# top.net
KiCad netlist of a schematic drawn in Altium Designer
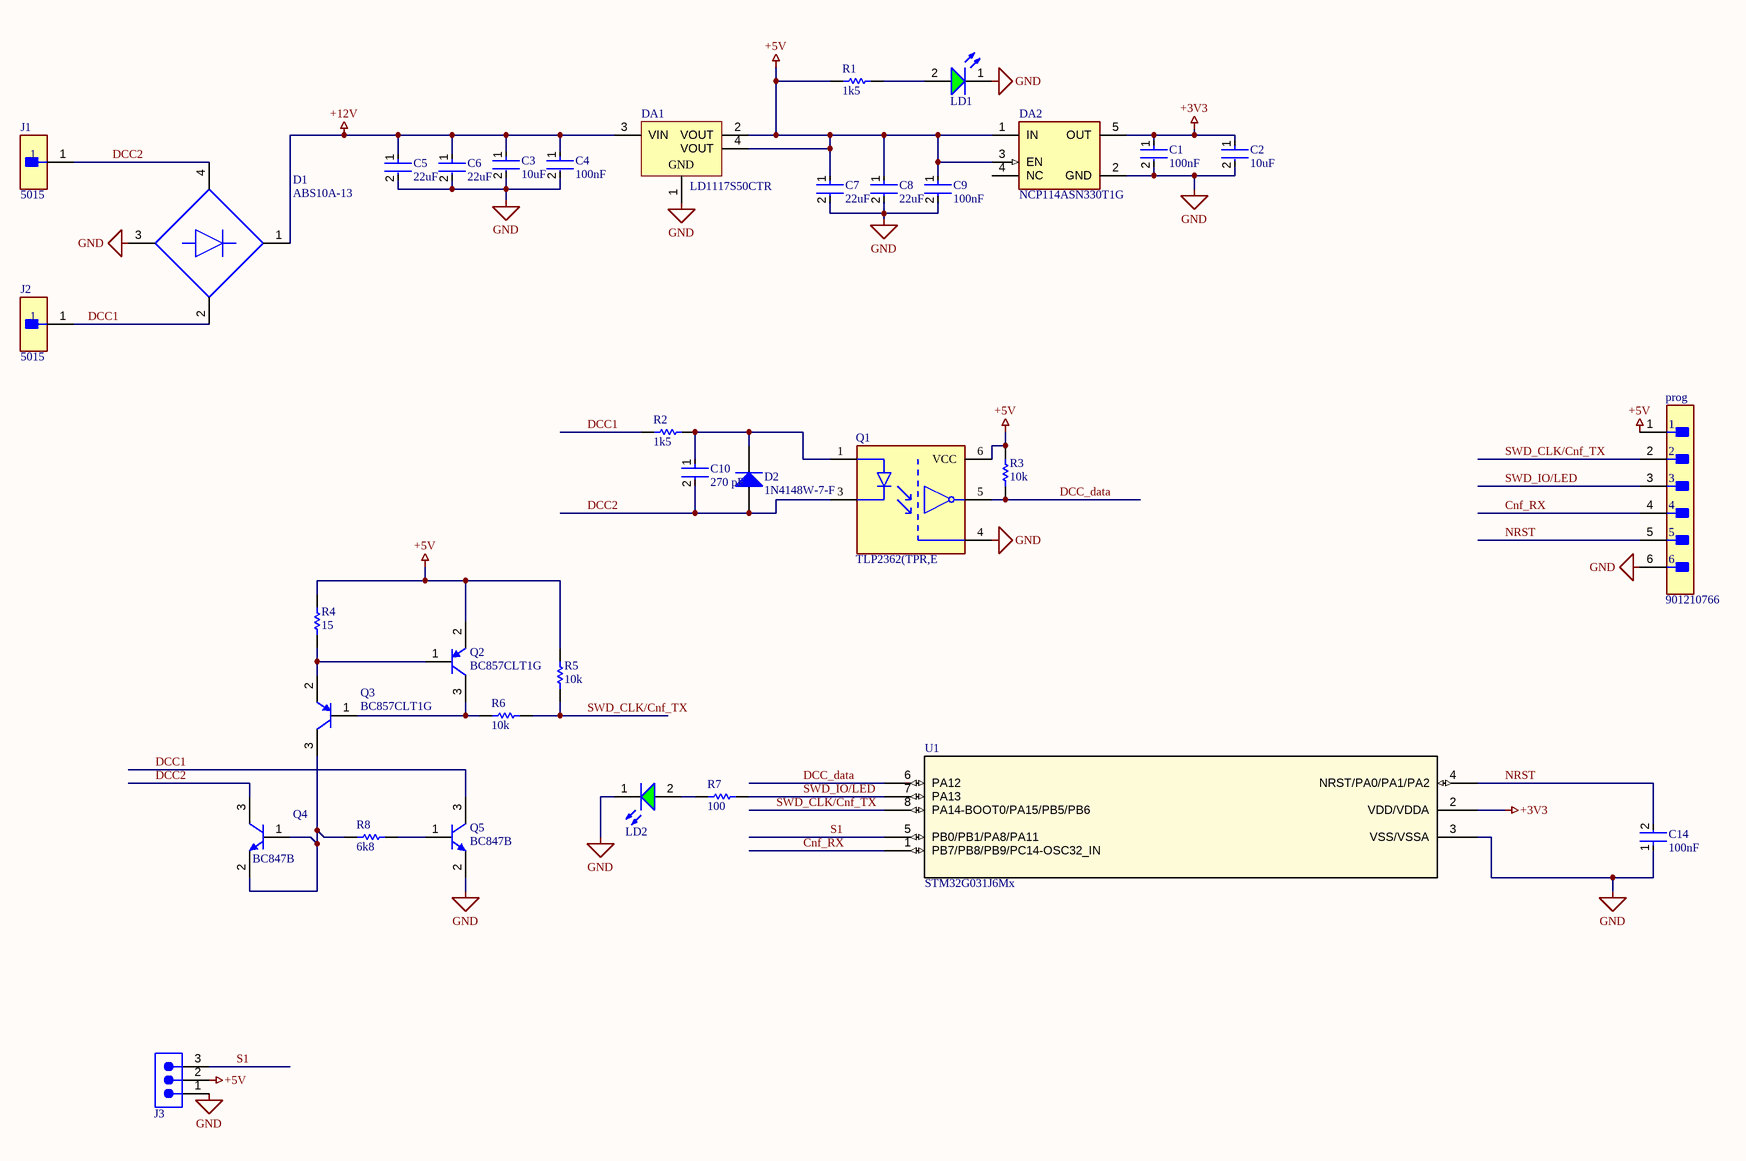
[diagram p0: top.SchDoc]

(export (version "E")
  (design (tool "Eeschema 10.0.6"))
  (components
    (comp (ref "C1")
      (value "CGA3E2X7R1H104K080AA")
      (footprint "FP-CGA3E-0_3-0_1-MFG")
      (description "Cap Ceramic 100nF 50V X7R 10% Pad SMD 0603 +125°C Automotive T/R")
      (fields
        (field (name "TOLERANCE") "10%")
        (field (name "CAPACITANCE") "100nF")
        (field (name "VOLTAGE") "50V")
      )
      (libsource (lib "Altium Content Vault") (part "b4654b650e69147ec39a6b967a45e02"))
    )
    (comp (ref "C2")
      (value "GRM188R60J106ME47D")
      (footprint "FP-GRM188-0_1-e0_2_0_55-MFG")
      (description "Chip Multilayer Ceramic Capacitors for General Purpose, 0603, 10uF, X5R, 15%, 20%, 6.3V")
      (fields
        (field (name "CAPACITANCE") "10uF")
        (field (name "VOLTAGE") "6.3V")
        (field (name "TOLERANCE") "20%")
      )
      (libsource (lib "Altium Content Vault") (part "02cd4be3c70576c341d710602a673aa"))
    )
    (comp (ref "C3")
      (value "GRM188R60J106ME47D")
      (footprint "FP-GRM188-0_1-e0_2_0_55-MFG")
      (description "Chip Multilayer Ceramic Capacitors for General Purpose, 0603, 10uF, X5R, 15%, 20%, 6.3V")
      (fields
        (field (name "CAPACITANCE") "10uF")
        (field (name "VOLTAGE") "6.3V")
        (field (name "TOLERANCE") "20%")
      )
      (libsource (lib "Altium Content Vault") (part "02cd4be3c70576c341d710602a673aa"))
    )
    (comp (ref "C4")
      (value "CGA3E2X7R1H104K080AA")
      (footprint "FP-CGA3E-0_3-0_1-MFG")
      (description "Cap Ceramic 100nF 50V X7R 10% Pad SMD 0603 +125°C Automotive T/R")
      (fields
        (field (name "TOLERANCE") "10%")
        (field (name "CAPACITANCE") "100nF")
        (field (name "VOLTAGE") "50V")
      )
      (libsource (lib "Altium Content Vault") (part "b4654b650e69147ec39a6b967a45e02"))
    )
    (comp (ref "C5")
      (value "GRM188R61A226ME15D")
      (footprint "FP-GRM188-0_2-MFG")
      (description "Chip Multilayer Ceramic Capacitors for General Purpose, 0603, 22uF, X5R, 15%, 20%, 10V")
      (fields (field (name "TOLERANCE") "20%") (field (name "CAPACITANCE") "22uF"))
      (libsource (lib "Altium Content Vault") (part "11868f565c42a9108669ba33697ecf6"))
    )
    (comp (ref "C6")
      (value "GRM188R61A226ME15D")
      (footprint "FP-GRM188-0_2-MFG")
      (description "Chip Multilayer Ceramic Capacitors for General Purpose, 0603, 22uF, X5R, 15%, 20%, 10V")
      (fields (field (name "TOLERANCE") "20%") (field (name "CAPACITANCE") "22uF"))
      (libsource (lib "Altium Content Vault") (part "11868f565c42a9108669ba33697ecf6"))
    )
    (comp (ref "C7")
      (value "GRM188R61A226ME15D")
      (footprint "FP-GRM188-0_2-MFG")
      (description "Chip Multilayer Ceramic Capacitors for General Purpose, 0603, 22uF, X5R, 15%, 20%, 10V")
      (fields (field (name "TOLERANCE") "20%") (field (name "CAPACITANCE") "22uF"))
      (libsource (lib "Altium Content Vault") (part "11868f565c42a9108669ba33697ecf6"))
    )
    (comp (ref "C8")
      (value "GRM188R61A226ME15D")
      (footprint "FP-GRM188-0_2-MFG")
      (description "Chip Multilayer Ceramic Capacitors for General Purpose, 0603, 22uF, X5R, 15%, 20%, 10V")
      (fields (field (name "TOLERANCE") "20%") (field (name "CAPACITANCE") "22uF"))
      (libsource (lib "Altium Content Vault") (part "11868f565c42a9108669ba33697ecf6"))
    )
    (comp (ref "C9")
      (value "CGA3E2X7R1H104K080AA")
      (footprint "FP-CGA3E-0_3-0_1-MFG")
      (description "Cap Ceramic 100nF 50V X7R 10% Pad SMD 0603 +125°C Automotive T/R")
      (fields
        (field (name "TOLERANCE") "10%")
        (field (name "CAPACITANCE") "100nF")
        (field (name "VOLTAGE") "50V")
      )
      (libsource (lib "Altium Content Vault") (part "b4654b650e69147ec39a6b967a45e02"))
    )
    (comp (ref "C10")
      (value "270 pF")
      (footprint "FP-C0603C-CF-IPC_C")
      (description "C0603 270 pF C0G 30ppm/°C 5.00% 50 V")
      (fields (field (name "MANUFACTURER PART NUMBER") "C0603C271J5GACTU"))
      (libsource (lib "Altium Content Vault") (part "b4654b650e69147ec39a6b967a45e02"))
    )
    (comp (ref "C14")
      (value "CGA3E2X7R1H104K080AA")
      (footprint "FP-CGA3E-0_3-0_1-MFG")
      (description "Cap Ceramic 100nF 50V X7R 10% Pad SMD 0603 +125°C Automotive T/R")
      (fields
        (field (name "TOLERANCE") "10%")
        (field (name "CAPACITANCE") "100nF")
        (field (name "VOLTAGE") "50V")
      )
      (libsource (lib "Altium Content Vault") (part "b4654b650e69147ec39a6b967a45e02"))
    )
    (comp (ref "D1")
      (value "ABS10A-13")
      (footprint "FP-SOPA-4-MFG")
      (description "BRIDGE RECT 1PHASE 1KV 1A 4SOPA")
      (libsource (lib "Altium Content Vault") (part "95261e4f58a5ffcdc7f7244183d0b96"))
    )
    (comp (ref "D2")
      (value "1N4148W-7-F")
      (footprint "DIOD-SOD123-2_V")
      (description "Fast Switching Diode, 100 V, 0.15 A, -65 to 150 degC, 2-Pin?SOD123, RoHS, Tape and Reel")
      (fields (field (name "MANUFACTURER") "DiodesIncorporated"))
      (libsource (lib "Altium Content Vault") (part "D-AK-2"))
    )
    (comp (ref "DA1")
      (value "LD1117S50CTR")
      (footprint "SOT-223_N")
      (description "Fixed Low Drop Positive Voltage Regulator, 5V, 4-Pin SOT-223, Tape and Reel")
      (libsource (lib "Altium Content Vault") (part "PM-REG-LD1117-SOT4"))
    )
    (comp (ref "DA2")
      (value "NCP114ASN330T1G")
      (footprint "FP-483-MFG")
      (description "IC REG LINEAR 3.3V 300MA 5TSOP")
      (fields
        (field (name "MANUFACTURER") "ON Semiconductor")
        (field (name "OCTOPART") "https://octopart.com/ncp114asn330t1g-on+semiconductor-74628742")
      )
      (libsource (lib "Altium Content Vault") (part "57814aa37072aacea77ef0fe9350350"))
    )
    (comp (ref "J1")
      (value "5015")
      (footprint "FP-5015-MFG")
      (description "PC TEST POINT MINIATURE")
      (fields
        (field (name "MANUFACTURER") "keystone")
        (field (name "OCTOPART") "https://octopart.com/5015-keystone-3822")
      )
      (libsource (lib "Altium Content Vault") (part "dd45045ce8184df9e99e12baf3f412c"))
    )
    (comp (ref "J2")
      (value "5015")
      (footprint "FP-5015-MFG")
      (description "PC TEST POINT MINIATURE")
      (fields
        (field (name "MANUFACTURER") "keystone")
        (field (name "OCTOPART") "https://octopart.com/5015-keystone-3822")
      )
      (libsource (lib "Altium Content Vault") (part "dd45045ce8184df9e99e12baf3f412c"))
    )
    (comp (ref "J3")
      (value "61300311021")
      (footprint "61300311021")
      (libsource (lib "Altium Content Vault") (part "Header_Male_1R_03P"))
    )
    (comp (ref "LD1")
      (value "150060VS75000")
      (footprint "WL-SMCW_0603_150060xx75000")
      (description "WURTH ELEKTRONIK - 150060VS75000 - LED, Green, SMD, 0603, 30 mA, 2 V, 570 nm")
      (libsource (lib "Altium Content Vault") (part "LED_Green_2A-1K"))
    )
    (comp (ref "LD2")
      (value "150060VS75000")
      (footprint "WL-SMCW_0603_150060xx75000")
      (description "WURTH ELEKTRONIK - 150060VS75000 - LED, Green, SMD, 0603, 30 mA, 2 V, 570 nm")
      (libsource (lib "Altium Content Vault") (part "LED_Green_2A-1K"))
    )
    (comp (ref "prog")
      (value "901210766")
      (footprint "FP-901210766-MFG")
      (description "CONN HEADER R/A 6POS 2.54MM")
      (fields
        (field (name "MANUFACTURER") "Molex")
        (field (name "OCTOPART") "https://octopart.com/90121-0766-molex-655456")
      )
      (libsource (lib "Altium Content Vault") (part "f2cb566baf1c37ab5a3b8e90bbeafd6"))
    )
    (comp (ref "Q1")
      (value "TLP2362(TPR,E")
      (footprint "FP-11-4L1S-MFG")
      (description "OPTOISO 3.75KV OPEN COLL SO6-5")
      (libsource (lib "Altium Content Vault") (part "1791dc5a774169b38fe9388fa91af9f"))
    )
    (comp (ref "Q2")
      (value "BC857CLT1G")
      (footprint "ONSC-SOT-23-3-318-08_V")
      (description "General Purpose Transistor, PNP Silicon, 3-Pin SOT-23, Pb-Free, Tape and Reel")
      (fields (field (name "MANUFACTURER") "On Semiconductor"))
      (libsource (lib "Altium Content Vault") (part "ONSC-PNP-B1E2C3-3"))
    )
    (comp (ref "Q3")
      (value "BC857CLT1G")
      (footprint "ONSC-SOT-23-3-318-08_V")
      (description "General Purpose Transistor, PNP Silicon, 3-Pin SOT-23, Pb-Free, Tape and Reel")
      (fields (field (name "MANUFACTURER") "On Semiconductor"))
      (libsource (lib "Altium Content Vault") (part "ONSC-PNP-B1E2C3-3"))
    )
    (comp (ref "Q4")
      (value "BC847B")
      (footprint "INF-SOT23_M")
      (description "NPN Silicon AF Transistor, 45 V VCEO, 100 mA IC, SOT23, Reel, Green")
      (fields (field (name "MANUFACTURER") "Infineon"))
      (libsource (lib "Altium Content Vault") (part "INF-BJTNPN-BEC-3"))
    )
    (comp (ref "Q5")
      (value "BC847B")
      (footprint "INF-SOT23_M")
      (description "NPN Silicon AF Transistor, 45 V VCEO, 100 mA IC, SOT23, Reel, Green")
      (fields (field (name "MANUFACTURER") "Infineon"))
      (libsource (lib "Altium Content Vault") (part "INF-BJTNPN-BEC-3"))
    )
    (comp (ref "R1")
      (value "1k5")
      (footprint "RESC1608X55X25ML10T15")
      (description "Chip Resistor, 1.5 KOhm, +/- 1%, 0.1 W, -55 to 155 degC, 0603 (1608 Metric), RoHS, Tape and Reel")
      (fields (field (name "TOLERANCE") "1%") (field (name "MANUFACTURER") "Yageo"))
      (libsource (lib "Altium Content Vault") (part "RES-2"))
    )
    (comp (ref "R2")
      (value "1k5")
      (footprint "RESC1608X55X25ML10T15")
      (description "Chip Resistor, 1.5 KOhm, +/- 1%, 0.1 W, -55 to 155 degC, 0603 (1608 Metric), RoHS, Tape and Reel")
      (fields (field (name "TOLERANCE") "1%") (field (name "MANUFACTURER") "Yageo"))
      (libsource (lib "Altium Content Vault") (part "RES-2"))
    )
    (comp (ref "R3")
      (value "10k")
      (footprint "RESC1609X55X30NL15T15")
      (description "Chip Resistor, 10 KOhm, +/- 1%, 0.1 W, -55 to 155 degC, 0603 (1608 Metric), RoHS, Tape and Reel")
      (fields (field (name "TOLERANCE") "1%") (field (name "MANUFACTURER") "Panasonic"))
      (libsource (lib "Altium Content Vault") (part "RES-2"))
    )
    (comp (ref "R4")
      (value "15")
      (footprint "RESC1608X55X30NL15T15")
      (fields (field (name "PART NUMBER") "ERJ-3EKF1502V") (field (name "MANUFACTURER") "Panasonic"))
      (libsource (lib "Altium Content Vault") (part "RES"))
    )
    (comp (ref "R5")
      (value "10k")
      (footprint "RESC1609X55X30NL15T15")
      (description "Chip Resistor, 10 KOhm, +/- 1%, 0.1 W, -55 to 155 degC, 0603 (1608 Metric), RoHS, Tape and Reel")
      (fields (field (name "TOLERANCE") "1%") (field (name "MANUFACTURER") "Panasonic"))
      (libsource (lib "Altium Content Vault") (part "RES-2"))
    )
    (comp (ref "R6")
      (value "10k")
      (footprint "RESC1609X55X30NL15T15")
      (description "Chip Resistor, 10 KOhm, +/- 1%, 0.1 W, -55 to 155 degC, 0603 (1608 Metric), RoHS, Tape and Reel")
      (fields (field (name "TOLERANCE") "1%") (field (name "MANUFACTURER") "Panasonic"))
      (libsource (lib "Altium Content Vault") (part "RES-2"))
    )
    (comp (ref "R7")
      (value "100")
      (footprint "RESC1608X55X30NL15T15")
      (fields (field (name "PART NUMBER") "ERJ-3EKF1003V") (field (name "MANUFACTURER") "Panasonic"))
      (libsource (lib "Altium Content Vault") (part "RES"))
    )
    (comp (ref "R8")
      (value "6k8")
      (footprint "RESC1608X55X25NL10T15")
      (description "Chip Resistor, 6.8 KOhm, +/- 1%, 100 mW, -55 to 155 degC, 0603 (1608 Metric), RoHS, Tape and Reel")
      (fields (field (name "Comment") "RC0603FR-076K8L"))
      (libsource (lib "Altium Content Vault") (part "RES-2"))
    )
    (comp (ref "U1")
      (value "STM32G031J6Mx")
      (footprint "SO-8")
      (fields
        (field (name "MANUFACTURER_PART_NUMBER") "stm32g0_so8_t1")
        (field (name "COPYRIGHT") "Copyright (C) 2018 Accelerated Designs. All rights reserved")
      )
      (libsource (lib "ST Microelectronics STM32 G0") (part "STM32G031J6Mx"))
    )
  )
  (nets
    (net (code "1") (name "+3V3") (class "Default")
      (node (ref "C1") (pin "1") (pinfunction "1_1") (pintype "passive"))
      (node (ref "C2") (pin "1") (pinfunction "1_1") (pintype "passive"))
      (node (ref "DA2") (pin "5") (pinfunction "OUT_5") (pintype "power_in"))
      (node (ref "U1") (pin "2") (pinfunction "VDD/VDDA_2") (pintype "power_in"))
    )
    (net (code "2") (name "+5V") (class "Default")
      (node (ref "C7") (pin "1") (pinfunction "1_1") (pintype "passive"))
      (node (ref "C8") (pin "1") (pinfunction "1_1") (pintype "passive"))
      (node (ref "C9") (pin "1") (pinfunction "1_1") (pintype "passive"))
      (node (ref "DA1") (pin "2") (pinfunction "VOUT_2") (pintype "power_in"))
      (node (ref "DA1") (pin "4") (pinfunction "VOUT_4") (pintype "power_in"))
      (node (ref "DA2") (pin "1") (pinfunction "IN_1") (pintype "power_in"))
      (node (ref "DA2") (pin "3") (pinfunction "EN_3") (pintype "input"))
      (node (ref "J3") (pin "2") (pinfunction "2_2") (pintype "passive"))
      (node (ref "Q1") (pin "6") (pinfunction "VCC_6") (pintype "power_in"))
      (node (ref "Q2") (pin "2") (pinfunction "E_2") (pintype "passive"))
      (node (ref "R1") (pin "1") (pinfunction "1_1") (pintype "passive"))
      (node (ref "R3") (pin "1") (pinfunction "1_1") (pintype "passive"))
      (node (ref "R4") (pin "2") (pinfunction "2_2") (pintype "passive"))
      (node (ref "R5") (pin "1") (pinfunction "1_1") (pintype "passive"))
      (node (ref "prog") (pin "1") (pinfunction "1_1") (pintype "passive"))
    )
    (net (code "3") (name "+12V") (class "Default")
      (node (ref "C3") (pin "1") (pinfunction "1_1") (pintype "passive"))
      (node (ref "C4") (pin "1") (pinfunction "1_1") (pintype "passive"))
      (node (ref "C5") (pin "1") (pinfunction "1_1") (pintype "passive"))
      (node (ref "C6") (pin "1") (pinfunction "1_1") (pintype "passive"))
      (node (ref "D1") (pin "1") (pinfunction "+_1") (pintype "passive"))
      (node (ref "DA1") (pin "3") (pinfunction "VIN_3") (pintype "power_in"))
    )
    (net (code "5") (name "/Cnf_RX") (class "Default")
      (node (ref "U1") (pin "1") (pinfunction "PB7/PB8/PB9/PC14-OSC32_IN_1") (pintype "bidirectional"))
      (node (ref "prog") (pin "4") (pinfunction "4_4") (pintype "passive"))
    )
    (net (code "6") (name "/DCC1") (class "Default")
      (node (ref "D1") (pin "2") (pinfunction "1_~_2") (pintype "passive"))
      (node (ref "J2") (pin "1") (pinfunction "1_1") (pintype "passive"))
      (node (ref "Q5") (pin "3") (pinfunction "C_3") (pintype "passive"))
      (node (ref "R2") (pin "1") (pinfunction "1_1") (pintype "passive"))
    )
    (net (code "7") (name "/DCC2") (class "Default")
      (node (ref "C10") (pin "2") (pinfunction "2_2") (pintype "passive"))
      (node (ref "D1") (pin "4") (pinfunction "2_~_4") (pintype "passive"))
      (node (ref "D2") (pin "1") (pinfunction "A_1") (pintype "passive"))
      (node (ref "J1") (pin "1") (pinfunction "1_1") (pintype "passive"))
      (node (ref "Q1") (pin "3") (pinfunction "C_3") (pintype "passive"))
      (node (ref "Q4") (pin "3") (pinfunction "C_3") (pintype "passive"))
    )
    (net (code "8") (name "/DCC_data") (class "Default")
      (node (ref "Q1") (pin "5") (pinfunction "Vo(output)_5") (pintype "passive"))
      (node (ref "R3") (pin "2") (pinfunction "2_2") (pintype "passive"))
      (node (ref "U1") (pin "6") (pinfunction "PA12_6") (pintype "bidirectional"))
    )
    (net (code "9") (name "/NRST") (class "Default")
      (node (ref "C14") (pin "2") (pinfunction "2_2") (pintype "passive"))
      (node (ref "U1") (pin "4") (pinfunction "NRST/PA0/PA1/PA2_4") (pintype "bidirectional"))
      (node (ref "prog") (pin "5") (pinfunction "5_5") (pintype "passive"))
    )
    (net (code "10") (name "/S1") (class "Default")
      (node (ref "J3") (pin "3") (pinfunction "3_3") (pintype "passive"))
      (node (ref "U1") (pin "5") (pinfunction "PB0/PB1/PA8/PA11_5") (pintype "bidirectional"))
    )
    (net (code "11") (name "/SWD_CLK{slash}Cnf_TX") (class "Default")
      (node (ref "R5") (pin "2") (pinfunction "2_2") (pintype "passive"))
      (node (ref "R6") (pin "1") (pinfunction "1_1") (pintype "passive"))
      (node (ref "U1") (pin "8") (pinfunction "PA14-BOOT0/PA15/PB5/PB6_8") (pintype "bidirectional"))
      (node (ref "prog") (pin "2") (pinfunction "2_2") (pintype "passive"))
    )
    (net (code "12") (name "/SWD_IO{slash}LED") (class "Default")
      (node (ref "R7") (pin "1") (pinfunction "1_1") (pintype "passive"))
      (node (ref "U1") (pin "7") (pinfunction "PA13_7") (pintype "bidirectional"))
      (node (ref "prog") (pin "3") (pinfunction "3_3") (pintype "passive"))
    )
    (net (code "13") (name "GND") (class "Default")
      (node (ref "C1") (pin "2") (pinfunction "2_2") (pintype "passive"))
      (node (ref "C14") (pin "1") (pinfunction "1_1") (pintype "passive"))
      (node (ref "C2") (pin "2") (pinfunction "2_2") (pintype "passive"))
      (node (ref "C3") (pin "2") (pinfunction "2_2") (pintype "passive"))
      (node (ref "C4") (pin "2") (pinfunction "2_2") (pintype "passive"))
      (node (ref "C5") (pin "2") (pinfunction "2_2") (pintype "passive"))
      (node (ref "C6") (pin "2") (pinfunction "2_2") (pintype "passive"))
      (node (ref "C7") (pin "2") (pinfunction "2_2") (pintype "passive"))
      (node (ref "C8") (pin "2") (pinfunction "2_2") (pintype "passive"))
      (node (ref "C9") (pin "2") (pinfunction "2_2") (pintype "passive"))
      (node (ref "D1") (pin "3") (pinfunction "-_3") (pintype "passive"))
      (node (ref "DA1") (pin "1") (pinfunction "GND_1") (pintype "power_in"))
      (node (ref "DA2") (pin "2") (pinfunction "GND_2") (pintype "power_in"))
      (node (ref "J3") (pin "1") (pinfunction "1_1") (pintype "passive"))
      (node (ref "LD1") (pin "1") (pinfunction "K_1") (pintype "passive"))
      (node (ref "LD2") (pin "1") (pinfunction "K_1") (pintype "passive"))
      (node (ref "Q1") (pin "4") (pinfunction "GND_4") (pintype "power_in"))
      (node (ref "Q5") (pin "2") (pinfunction "E_2") (pintype "passive"))
      (node (ref "U1") (pin "3") (pinfunction "VSS/VSSA_3") (pintype "power_in"))
      (node (ref "prog") (pin "6") (pinfunction "6_6") (pintype "passive"))
    )
    (net (code "14") (name "Net-(D2-K)") (class "Default")
      (node (ref "C10") (pin "1") (pinfunction "1_1") (pintype "passive"))
      (node (ref "D2") (pin "2") (pinfunction "K_2") (pintype "passive"))
      (node (ref "Q1") (pin "1") (pinfunction "A_1") (pintype "passive"))
      (node (ref "R2") (pin "2") (pinfunction "2_2") (pintype "passive"))
    )
    (net (code "15") (name "Net-(LD1-A)") (class "Default")
      (node (ref "LD1") (pin "2") (pinfunction "A_2") (pintype "passive"))
      (node (ref "R1") (pin "2") (pinfunction "2_2") (pintype "passive"))
    )
    (net (code "16") (name "Net-(LD2-A)") (class "Default")
      (node (ref "LD2") (pin "2") (pinfunction "A_2") (pintype "passive"))
      (node (ref "R7") (pin "2") (pinfunction "2_2") (pintype "passive"))
    )
    (net (code "17") (name "Net-(Q2-B)") (class "Default")
      (node (ref "Q2") (pin "1") (pinfunction "B_1") (pintype "passive"))
      (node (ref "Q3") (pin "2") (pinfunction "E_2") (pintype "passive"))
      (node (ref "R4") (pin "1") (pinfunction "1_1") (pintype "passive"))
    )
    (net (code "18") (name "Net-(Q2-C)") (class "Default")
      (node (ref "Q2") (pin "3") (pinfunction "C_3") (pintype "passive"))
      (node (ref "Q3") (pin "1") (pinfunction "B_1") (pintype "passive"))
      (node (ref "R6") (pin "2") (pinfunction "2_2") (pintype "passive"))
    )
    (net (code "19") (name "Net-(Q3-C)") (class "Default")
      (node (ref "Q3") (pin "3") (pinfunction "C_3") (pintype "passive"))
      (node (ref "Q4") (pin "1") (pinfunction "B_1") (pintype "passive"))
      (node (ref "Q4") (pin "2") (pinfunction "E_2") (pintype "passive"))
      (node (ref "R8") (pin "1") (pinfunction "1_1") (pintype "passive"))
    )
    (net (code "20") (name "Net-(Q5-B)") (class "Default")
      (node (ref "Q5") (pin "1") (pinfunction "B_1") (pintype "passive"))
      (node (ref "R8") (pin "2") (pinfunction "2_2") (pintype "passive"))
    )
    (net (code "21") (name "unconnected-(DA2-NC-Pad4)") (class "Default")
      (node (ref "DA2") (pin "4") (pinfunction "NC_4") (pintype "passive"))
    )
  )
)
